# W101A.net
KiCad netlist of a schematic drawn in EAGLE
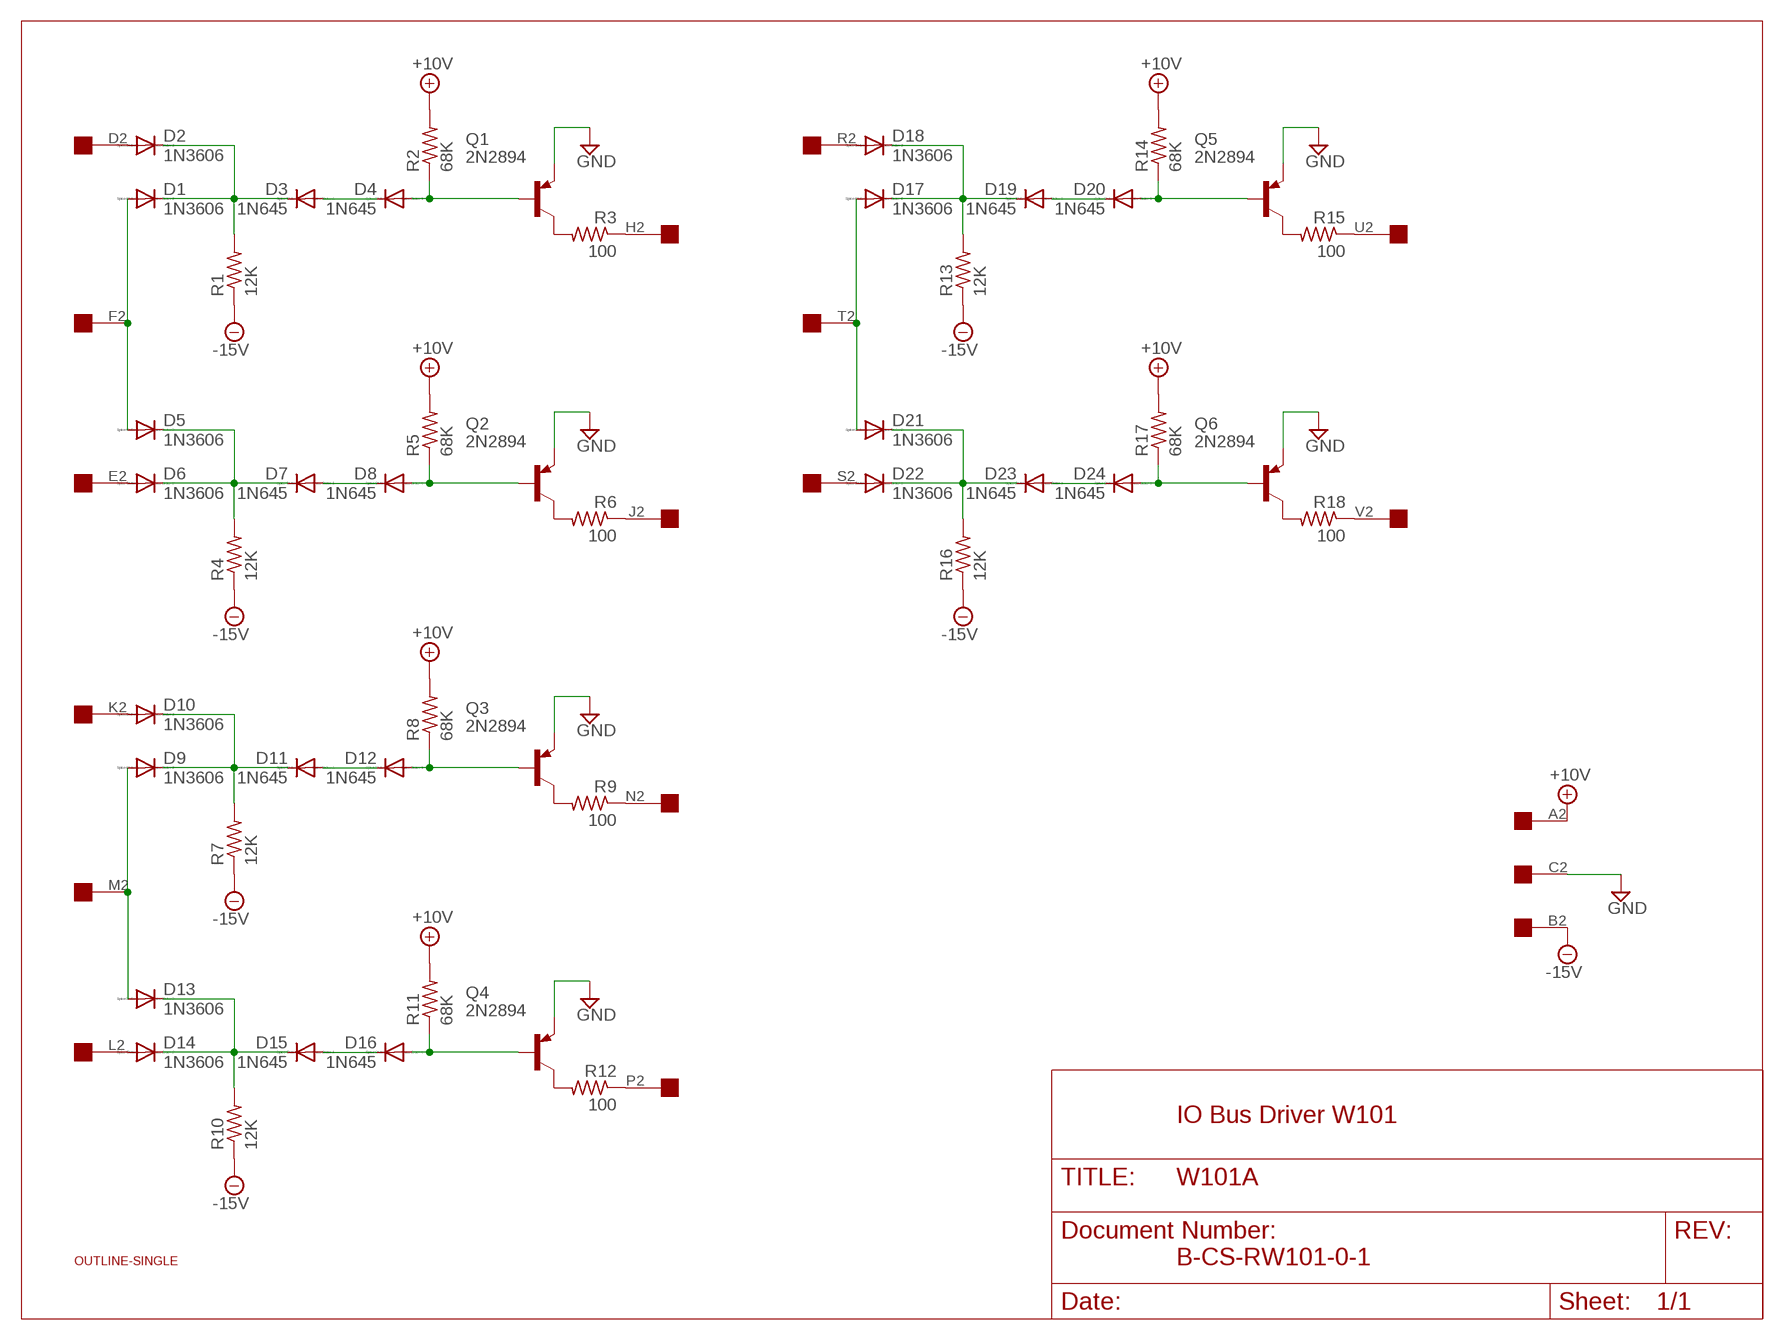
[diagram p0: schematic, sheet 1]

(export (version "E")
  (design (tool "Eeschema 10.0.6"))
  (components
    (comp (ref "D1")
      (value "1N3606")
      (footprint "eagle-import:DO35-10")
      (libsource (lib "eagle-import") (part "1N4148DO35-10"))
    )
    (comp (ref "D2")
      (value "1N3606")
      (footprint "eagle-import:DO35-10")
      (libsource (lib "eagle-import") (part "1N4148DO35-10"))
    )
    (comp (ref "D3")
      (value "1N645")
      (footprint "eagle-import:DO35-10")
      (libsource (lib "eagle-import") (part "1N4148DO35-10"))
    )
    (comp (ref "D4")
      (value "1N645")
      (footprint "eagle-import:DO35-10")
      (libsource (lib "eagle-import") (part "1N4148DO35-10"))
    )
    (comp (ref "D5")
      (value "1N3606")
      (footprint "eagle-import:DO35-10")
      (libsource (lib "eagle-import") (part "1N4148DO35-10"))
    )
    (comp (ref "D6")
      (value "1N3606")
      (footprint "eagle-import:DO35-10")
      (libsource (lib "eagle-import") (part "1N4148DO35-10"))
    )
    (comp (ref "D7")
      (value "1N645")
      (footprint "eagle-import:DO35-10")
      (libsource (lib "eagle-import") (part "1N4148DO35-10"))
    )
    (comp (ref "D8")
      (value "1N645")
      (footprint "eagle-import:DO35-10")
      (libsource (lib "eagle-import") (part "1N4148DO35-10"))
    )
    (comp (ref "D9")
      (value "1N3606")
      (footprint "eagle-import:DO35-10")
      (libsource (lib "eagle-import") (part "1N4148DO35-10"))
    )
    (comp (ref "D10")
      (value "1N3606")
      (footprint "eagle-import:DO35-10")
      (libsource (lib "eagle-import") (part "1N4148DO35-10"))
    )
    (comp (ref "D11")
      (value "1N645")
      (footprint "eagle-import:DO35-10")
      (libsource (lib "eagle-import") (part "1N4148DO35-10"))
    )
    (comp (ref "D12")
      (value "1N645")
      (footprint "eagle-import:DO35-10")
      (libsource (lib "eagle-import") (part "1N4148DO35-10"))
    )
    (comp (ref "D13")
      (value "1N3606")
      (footprint "eagle-import:DO35-10")
      (libsource (lib "eagle-import") (part "1N4148DO35-10"))
    )
    (comp (ref "D14")
      (value "1N3606")
      (footprint "eagle-import:DO35-10")
      (libsource (lib "eagle-import") (part "1N4148DO35-10"))
    )
    (comp (ref "D15")
      (value "1N645")
      (footprint "eagle-import:DO35-10")
      (libsource (lib "eagle-import") (part "1N4148DO35-10"))
    )
    (comp (ref "D16")
      (value "1N645")
      (footprint "eagle-import:DO35-10")
      (libsource (lib "eagle-import") (part "1N4148DO35-10"))
    )
    (comp (ref "D17")
      (value "1N3606")
      (footprint "eagle-import:DO35-10")
      (libsource (lib "eagle-import") (part "1N4148DO35-10"))
    )
    (comp (ref "D18")
      (value "1N3606")
      (footprint "eagle-import:DO35-10")
      (libsource (lib "eagle-import") (part "1N4148DO35-10"))
    )
    (comp (ref "D19")
      (value "1N645")
      (footprint "eagle-import:DO35-10")
      (libsource (lib "eagle-import") (part "1N4148DO35-10"))
    )
    (comp (ref "D20")
      (value "1N645")
      (footprint "eagle-import:DO35-10")
      (libsource (lib "eagle-import") (part "1N4148DO35-10"))
    )
    (comp (ref "D21")
      (value "1N3606")
      (footprint "eagle-import:DO35-10")
      (libsource (lib "eagle-import") (part "1N4148DO35-10"))
    )
    (comp (ref "D22")
      (value "1N3606")
      (footprint "eagle-import:DO35-10")
      (libsource (lib "eagle-import") (part "1N4148DO35-10"))
    )
    (comp (ref "D23")
      (value "1N645")
      (footprint "eagle-import:DO35-10")
      (libsource (lib "eagle-import") (part "1N4148DO35-10"))
    )
    (comp (ref "D24")
      (value "1N645")
      (footprint "eagle-import:DO35-10")
      (libsource (lib "eagle-import") (part "1N4148DO35-10"))
    )
    (comp (ref "Q1")
      (value "2N2894")
      (footprint "eagle-import:TO39")
      (libsource (lib "eagle-import") (part "2N3637"))
    )
    (comp (ref "Q2")
      (value "2N2894")
      (footprint "eagle-import:TO39")
      (libsource (lib "eagle-import") (part "2N3637"))
    )
    (comp (ref "Q3")
      (value "2N2894")
      (footprint "eagle-import:TO39")
      (libsource (lib "eagle-import") (part "2N3637"))
    )
    (comp (ref "Q4")
      (value "2N2894")
      (footprint "eagle-import:TO39")
      (libsource (lib "eagle-import") (part "2N3637"))
    )
    (comp (ref "Q5")
      (value "2N2894")
      (footprint "eagle-import:TO39")
      (libsource (lib "eagle-import") (part "2N3637"))
    )
    (comp (ref "Q6")
      (value "2N2894")
      (footprint "eagle-import:TO39")
      (libsource (lib "eagle-import") (part "2N3637"))
    )
    (comp (ref "R1")
      (value "12K")
      (footprint "eagle-import:0207_10")
      (libsource (lib "eagle-import") (part "R-US_0207/10"))
    )
    (comp (ref "R2")
      (value "68K")
      (footprint "eagle-import:0207_10")
      (libsource (lib "eagle-import") (part "R-US_0207/10"))
    )
    (comp (ref "R3")
      (value "100")
      (footprint "eagle-import:0207_10")
      (libsource (lib "eagle-import") (part "R-US_0207/10"))
    )
    (comp (ref "R4")
      (value "12K")
      (footprint "eagle-import:0207_10")
      (libsource (lib "eagle-import") (part "R-US_0207/10"))
    )
    (comp (ref "R5")
      (value "68K")
      (footprint "eagle-import:0207_10")
      (libsource (lib "eagle-import") (part "R-US_0207/10"))
    )
    (comp (ref "R6")
      (value "100")
      (footprint "eagle-import:0207_10")
      (libsource (lib "eagle-import") (part "R-US_0207/10"))
    )
    (comp (ref "R7")
      (value "12K")
      (footprint "eagle-import:0207_10")
      (libsource (lib "eagle-import") (part "R-US_0207/10"))
    )
    (comp (ref "R8")
      (value "68K")
      (footprint "eagle-import:0207_10")
      (libsource (lib "eagle-import") (part "R-US_0207/10"))
    )
    (comp (ref "R9")
      (value "100")
      (footprint "eagle-import:0207_10")
      (libsource (lib "eagle-import") (part "R-US_0207/10"))
    )
    (comp (ref "R10")
      (value "12K")
      (footprint "eagle-import:0207_10")
      (libsource (lib "eagle-import") (part "R-US_0207/10"))
    )
    (comp (ref "R11")
      (value "68K")
      (footprint "eagle-import:0207_10")
      (libsource (lib "eagle-import") (part "R-US_0207/10"))
    )
    (comp (ref "R12")
      (value "100")
      (footprint "eagle-import:0207_10")
      (libsource (lib "eagle-import") (part "R-US_0207/10"))
    )
    (comp (ref "R13")
      (value "12K")
      (footprint "eagle-import:0207_10")
      (libsource (lib "eagle-import") (part "R-US_0207/10"))
    )
    (comp (ref "R14")
      (value "68K")
      (footprint "eagle-import:0207_10")
      (libsource (lib "eagle-import") (part "R-US_0207/10"))
    )
    (comp (ref "R15")
      (value "100")
      (footprint "eagle-import:0207_10")
      (libsource (lib "eagle-import") (part "R-US_0207/10"))
    )
    (comp (ref "R16")
      (value "12K")
      (footprint "eagle-import:0207_10")
      (libsource (lib "eagle-import") (part "R-US_0207/10"))
    )
    (comp (ref "R17")
      (value "68K")
      (footprint "eagle-import:0207_10")
      (libsource (lib "eagle-import") (part "R-US_0207/10"))
    )
    (comp (ref "R18")
      (value "100")
      (footprint "eagle-import:0207_10")
      (libsource (lib "eagle-import") (part "R-US_0207/10"))
    )
    (comp (ref "U$1")
      (value "OUTLINE-SINGLE")
      (footprint "eagle-import:SINGLE")
      (libsource (lib "eagle-import") (part "OUTLINE-SINGLE"))
    )
    (comp (ref "U$2")
      (value "EDGE-1")
      (footprint "eagle-import:EDGE-CON1")
      (libsource (lib "eagle-import") (part "EDGE-1"))
    )
  )
  (nets
    (net (code "1") (name "+10V") (class "Default")
      (node (ref "R11") (pin "2") (pinfunction "2_2") (pintype "passive"))
      (node (ref "R14") (pin "2") (pinfunction "2_2") (pintype "passive"))
      (node (ref "R17") (pin "2") (pinfunction "2_2") (pintype "passive"))
      (node (ref "R2") (pin "2") (pinfunction "2_2") (pintype "passive"))
      (node (ref "R5") (pin "2") (pinfunction "2_2") (pintype "passive"))
      (node (ref "R8") (pin "2") (pinfunction "2_2") (pintype "passive"))
      (node (ref "U$2") (pin "A2") (pinfunction "1_A2") (pintype "bidirectional"))
    )
    (net (code "2") (name "-15V") (class "Default")
      (node (ref "R1") (pin "1") (pinfunction "1_1") (pintype "passive"))
      (node (ref "R10") (pin "1") (pinfunction "1_1") (pintype "passive"))
      (node (ref "R13") (pin "1") (pinfunction "1_1") (pintype "passive"))
      (node (ref "R16") (pin "1") (pinfunction "1_1") (pintype "passive"))
      (node (ref "R4") (pin "1") (pinfunction "1_1") (pintype "passive"))
      (node (ref "R7") (pin "1") (pinfunction "1_1") (pintype "passive"))
      (node (ref "U$2") (pin "B2") (pinfunction "1_B2") (pintype "bidirectional"))
    )
    (net (code "3") (name "GND") (class "Default")
      (node (ref "Q1") (pin "1") (pinfunction "E_1") (pintype "passive"))
      (node (ref "Q2") (pin "1") (pinfunction "E_1") (pintype "passive"))
      (node (ref "Q3") (pin "1") (pinfunction "E_1") (pintype "passive"))
      (node (ref "Q4") (pin "1") (pinfunction "E_1") (pintype "passive"))
      (node (ref "Q5") (pin "1") (pinfunction "E_1") (pintype "passive"))
      (node (ref "Q6") (pin "1") (pinfunction "E_1") (pintype "passive"))
      (node (ref "U$2") (pin "C2") (pinfunction "1_C2") (pintype "bidirectional"))
    )
    (net (code "4") (name "Net-(D1-PadC)") (class "Default")
      (node (ref "D1") (pin "C") (pinfunction "C_C") (pintype "passive"))
      (node (ref "D2") (pin "C") (pinfunction "C_C") (pintype "passive"))
      (node (ref "D3") (pin "C") (pinfunction "C_C") (pintype "passive"))
      (node (ref "R1") (pin "2") (pinfunction "2_2") (pintype "passive"))
    )
    (net (code "5") (name "Net-(D3-PadA)") (class "Default")
      (node (ref "D3") (pin "A") (pinfunction "A_A") (pintype "passive"))
      (node (ref "D4") (pin "C") (pinfunction "C_C") (pintype "passive"))
    )
    (net (code "6") (name "Net-(D5-PadC)") (class "Default")
      (node (ref "D5") (pin "C") (pinfunction "C_C") (pintype "passive"))
      (node (ref "D6") (pin "C") (pinfunction "C_C") (pintype "passive"))
      (node (ref "D7") (pin "C") (pinfunction "C_C") (pintype "passive"))
      (node (ref "R4") (pin "2") (pinfunction "2_2") (pintype "passive"))
    )
    (net (code "7") (name "Net-(D7-PadA)") (class "Default")
      (node (ref "D7") (pin "A") (pinfunction "A_A") (pintype "passive"))
      (node (ref "D8") (pin "C") (pinfunction "C_C") (pintype "passive"))
    )
    (net (code "8") (name "Net-(D10-PadC)") (class "Default")
      (node (ref "D10") (pin "C") (pinfunction "C_C") (pintype "passive"))
      (node (ref "D11") (pin "C") (pinfunction "C_C") (pintype "passive"))
      (node (ref "D9") (pin "C") (pinfunction "C_C") (pintype "passive"))
      (node (ref "R7") (pin "2") (pinfunction "2_2") (pintype "passive"))
    )
    (net (code "9") (name "Net-(D11-PadA)") (class "Default")
      (node (ref "D11") (pin "A") (pinfunction "A_A") (pintype "passive"))
      (node (ref "D12") (pin "C") (pinfunction "C_C") (pintype "passive"))
    )
    (net (code "10") (name "Net-(D13-PadC)") (class "Default")
      (node (ref "D13") (pin "C") (pinfunction "C_C") (pintype "passive"))
      (node (ref "D14") (pin "C") (pinfunction "C_C") (pintype "passive"))
      (node (ref "D15") (pin "C") (pinfunction "C_C") (pintype "passive"))
      (node (ref "R10") (pin "2") (pinfunction "2_2") (pintype "passive"))
    )
    (net (code "11") (name "Net-(D15-PadA)") (class "Default")
      (node (ref "D15") (pin "A") (pinfunction "A_A") (pintype "passive"))
      (node (ref "D16") (pin "C") (pinfunction "C_C") (pintype "passive"))
    )
    (net (code "12") (name "Net-(D17-PadC)") (class "Default")
      (node (ref "D17") (pin "C") (pinfunction "C_C") (pintype "passive"))
      (node (ref "D18") (pin "C") (pinfunction "C_C") (pintype "passive"))
      (node (ref "D19") (pin "C") (pinfunction "C_C") (pintype "passive"))
      (node (ref "R13") (pin "2") (pinfunction "2_2") (pintype "passive"))
    )
    (net (code "13") (name "Net-(D19-PadA)") (class "Default")
      (node (ref "D19") (pin "A") (pinfunction "A_A") (pintype "passive"))
      (node (ref "D20") (pin "C") (pinfunction "C_C") (pintype "passive"))
    )
    (net (code "14") (name "Net-(D21-PadC)") (class "Default")
      (node (ref "D21") (pin "C") (pinfunction "C_C") (pintype "passive"))
      (node (ref "D22") (pin "C") (pinfunction "C_C") (pintype "passive"))
      (node (ref "D23") (pin "C") (pinfunction "C_C") (pintype "passive"))
      (node (ref "R16") (pin "2") (pinfunction "2_2") (pintype "passive"))
    )
    (net (code "15") (name "Net-(D23-PadA)") (class "Default")
      (node (ref "D23") (pin "A") (pinfunction "A_A") (pintype "passive"))
      (node (ref "D24") (pin "C") (pinfunction "C_C") (pintype "passive"))
    )
    (net (code "16") (name "Net-(Q1-B)") (class "Default")
      (node (ref "D4") (pin "A") (pinfunction "A_A") (pintype "passive"))
      (node (ref "Q1") (pin "2") (pinfunction "B_2") (pintype "passive"))
      (node (ref "R2") (pin "1") (pinfunction "1_1") (pintype "passive"))
    )
    (net (code "17") (name "Net-(Q1-C)") (class "Default")
      (node (ref "Q1") (pin "3") (pinfunction "C_3") (pintype "passive"))
      (node (ref "R3") (pin "2") (pinfunction "2_2") (pintype "passive"))
    )
    (net (code "18") (name "Net-(Q2-B)") (class "Default")
      (node (ref "D8") (pin "A") (pinfunction "A_A") (pintype "passive"))
      (node (ref "Q2") (pin "2") (pinfunction "B_2") (pintype "passive"))
      (node (ref "R5") (pin "1") (pinfunction "1_1") (pintype "passive"))
    )
    (net (code "19") (name "Net-(Q2-C)") (class "Default")
      (node (ref "Q2") (pin "3") (pinfunction "C_3") (pintype "passive"))
      (node (ref "R6") (pin "2") (pinfunction "2_2") (pintype "passive"))
    )
    (net (code "20") (name "Net-(Q3-B)") (class "Default")
      (node (ref "D12") (pin "A") (pinfunction "A_A") (pintype "passive"))
      (node (ref "Q3") (pin "2") (pinfunction "B_2") (pintype "passive"))
      (node (ref "R8") (pin "1") (pinfunction "1_1") (pintype "passive"))
    )
    (net (code "21") (name "Net-(Q3-C)") (class "Default")
      (node (ref "Q3") (pin "3") (pinfunction "C_3") (pintype "passive"))
      (node (ref "R9") (pin "2") (pinfunction "2_2") (pintype "passive"))
    )
    (net (code "22") (name "Net-(Q4-B)") (class "Default")
      (node (ref "D16") (pin "A") (pinfunction "A_A") (pintype "passive"))
      (node (ref "Q4") (pin "2") (pinfunction "B_2") (pintype "passive"))
      (node (ref "R11") (pin "1") (pinfunction "1_1") (pintype "passive"))
    )
    (net (code "23") (name "Net-(Q4-C)") (class "Default")
      (node (ref "Q4") (pin "3") (pinfunction "C_3") (pintype "passive"))
      (node (ref "R12") (pin "2") (pinfunction "2_2") (pintype "passive"))
    )
    (net (code "24") (name "Net-(Q5-B)") (class "Default")
      (node (ref "D20") (pin "A") (pinfunction "A_A") (pintype "passive"))
      (node (ref "Q5") (pin "2") (pinfunction "B_2") (pintype "passive"))
      (node (ref "R14") (pin "1") (pinfunction "1_1") (pintype "passive"))
    )
    (net (code "25") (name "Net-(Q5-C)") (class "Default")
      (node (ref "Q5") (pin "3") (pinfunction "C_3") (pintype "passive"))
      (node (ref "R15") (pin "2") (pinfunction "2_2") (pintype "passive"))
    )
    (net (code "26") (name "Net-(Q6-B)") (class "Default")
      (node (ref "D24") (pin "A") (pinfunction "A_A") (pintype "passive"))
      (node (ref "Q6") (pin "2") (pinfunction "B_2") (pintype "passive"))
      (node (ref "R17") (pin "1") (pinfunction "1_1") (pintype "passive"))
    )
    (net (code "27") (name "Net-(Q6-C)") (class "Default")
      (node (ref "Q6") (pin "3") (pinfunction "C_3") (pintype "passive"))
      (node (ref "R18") (pin "2") (pinfunction "2_2") (pintype "passive"))
    )
    (net (code "28") (name "Net-(U$2D-1)") (class "Default")
      (node (ref "D2") (pin "A") (pinfunction "A_A") (pintype "passive"))
      (node (ref "U$2") (pin "D2") (pinfunction "1_D2") (pintype "bidirectional"))
    )
    (net (code "29") (name "Net-(U$2E-1)") (class "Default")
      (node (ref "D6") (pin "A") (pinfunction "A_A") (pintype "passive"))
      (node (ref "U$2") (pin "E2") (pinfunction "1_E2") (pintype "bidirectional"))
    )
    (net (code "30") (name "Net-(U$2F-1)") (class "Default")
      (node (ref "D1") (pin "A") (pinfunction "A_A") (pintype "passive"))
      (node (ref "D5") (pin "A") (pinfunction "A_A") (pintype "passive"))
      (node (ref "U$2") (pin "F2") (pinfunction "1_F2") (pintype "bidirectional"))
    )
    (net (code "31") (name "Net-(U$2G-1)") (class "Default")
      (node (ref "R3") (pin "1") (pinfunction "1_1") (pintype "passive"))
      (node (ref "U$2") (pin "H2") (pinfunction "1_H2") (pintype "bidirectional"))
    )
    (net (code "32") (name "Net-(U$2H-1)") (class "Default")
      (node (ref "R6") (pin "1") (pinfunction "1_1") (pintype "passive"))
      (node (ref "U$2") (pin "J2") (pinfunction "1_J2") (pintype "bidirectional"))
    )
    (net (code "33") (name "Net-(U$2I-1)") (class "Default")
      (node (ref "D10") (pin "A") (pinfunction "A_A") (pintype "passive"))
      (node (ref "U$2") (pin "K2") (pinfunction "1_K2") (pintype "bidirectional"))
    )
    (net (code "34") (name "Net-(U$2J-1)") (class "Default")
      (node (ref "D14") (pin "A") (pinfunction "A_A") (pintype "passive"))
      (node (ref "U$2") (pin "L2") (pinfunction "1_L2") (pintype "bidirectional"))
    )
    (net (code "35") (name "Net-(U$2K-1)") (class "Default")
      (node (ref "D13") (pin "A") (pinfunction "A_A") (pintype "passive"))
      (node (ref "D9") (pin "A") (pinfunction "A_A") (pintype "passive"))
      (node (ref "U$2") (pin "M2") (pinfunction "1_M2") (pintype "bidirectional"))
    )
    (net (code "36") (name "Net-(U$2L-1)") (class "Default")
      (node (ref "R9") (pin "1") (pinfunction "1_1") (pintype "passive"))
      (node (ref "U$2") (pin "N2") (pinfunction "1_N2") (pintype "bidirectional"))
    )
    (net (code "37") (name "Net-(U$2M-1)") (class "Default")
      (node (ref "R12") (pin "1") (pinfunction "1_1") (pintype "passive"))
      (node (ref "U$2") (pin "P2") (pinfunction "1_P2") (pintype "bidirectional"))
    )
    (net (code "38") (name "Net-(U$2N-1)") (class "Default")
      (node (ref "D18") (pin "A") (pinfunction "A_A") (pintype "passive"))
      (node (ref "U$2") (pin "R2") (pinfunction "1_R2") (pintype "bidirectional"))
    )
    (net (code "39") (name "Net-(U$2O-1)") (class "Default")
      (node (ref "D22") (pin "A") (pinfunction "A_A") (pintype "passive"))
      (node (ref "U$2") (pin "S2") (pinfunction "1_S2") (pintype "bidirectional"))
    )
    (net (code "40") (name "Net-(U$2P-1)") (class "Default")
      (node (ref "D17") (pin "A") (pinfunction "A_A") (pintype "passive"))
      (node (ref "D21") (pin "A") (pinfunction "A_A") (pintype "passive"))
      (node (ref "U$2") (pin "T2") (pinfunction "1_T2") (pintype "bidirectional"))
    )
    (net (code "41") (name "Net-(U$2Q-1)") (class "Default")
      (node (ref "R15") (pin "1") (pinfunction "1_1") (pintype "passive"))
      (node (ref "U$2") (pin "U2") (pinfunction "1_U2") (pintype "bidirectional"))
    )
    (net (code "42") (name "Net-(U$2R-1)") (class "Default")
      (node (ref "R18") (pin "1") (pinfunction "1_1") (pintype "passive"))
      (node (ref "U$2") (pin "V2") (pinfunction "1_V2") (pintype "bidirectional"))
    )
  )
)
